# LPM_CLK.net
KiCad netlist of a schematic drawn in Altium Designer
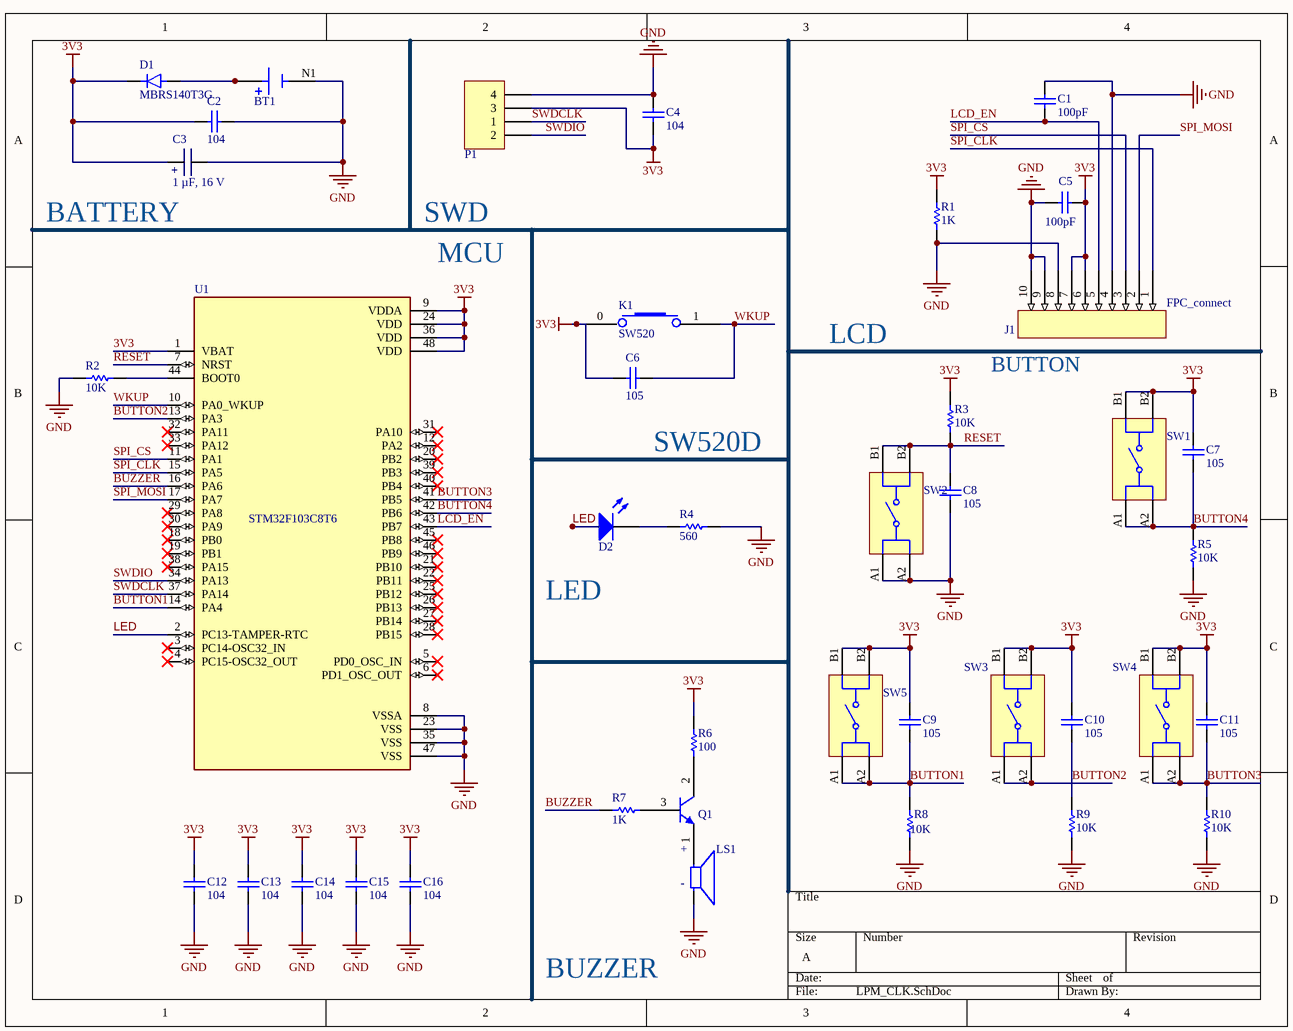
[diagram p0: LPM_CLK.SchDoc]

(export (version "E")
  (design (tool "Eeschema 10.0.6"))
  (components
    (comp (ref "BT1")
      (value "BAT-HLD-001")
      (footprint "BAT_BAT-HLD-001")
      (description "Battery Retainer Coin, 20.0mm 1 Cell SMD (SMT) Tab")
      (libsource (lib "BAT-HLD-001") (part "BAT-HLD-001"))
    )
    (comp (ref "C1")
      (value "100pF")
      (footprint "CAP-SM-0805")
      (description "Capacitor")
      (fields (field (name "Comment") "Cap Non-Pol SMD"))
      (libsource (lib "PIF_Library") (part "Cap Non-Pol SMD"))
    )
    (comp (ref "C2")
      (value "104")
      (footprint "CAP-SM-0805")
      (description "Capacitor")
      (fields (field (name "Comment") "Cap Non-Pol SMD"))
      (libsource (lib "PIF_Library") (part "Cap Non-Pol SMD"))
    )
    (comp (ref "C3")
      (value "1 µF, 16 V")
      (footprint "TANTALUM SMD A")
      (description "CAP TANT 1uF 10% 16V 1206")
      (libsource (lib "Altium_Tanta_Capacitor") (part "01120610510"))
    )
    (comp (ref "C4")
      (value "104")
      (footprint "CAP-SM-0805")
      (description "Capacitor")
      (fields (field (name "Comment") "Cap Non-Pol SMD"))
      (libsource (lib "PIF_Library") (part "Cap Non-Pol SMD"))
    )
    (comp (ref "C5")
      (value "100pF")
      (footprint "CAP-SM-0805")
      (description "Capacitor")
      (fields (field (name "Comment") "Cap Non-Pol SMD"))
      (libsource (lib "PIF_Library") (part "Cap Non-Pol SMD"))
    )
    (comp (ref "C6")
      (value "105")
      (footprint "CAP-SM-0805")
      (description "Capacitor")
      (fields (field (name "Comment") "Cap Non-Pol SMD"))
      (libsource (lib "PIF_Library") (part "Cap Non-Pol SMD"))
    )
    (comp (ref "C7")
      (value "105")
      (footprint "CAP-SM-0805")
      (description "Capacitor")
      (fields (field (name "Comment") "Cap Non-Pol SMD"))
      (libsource (lib "PIF_Library") (part "Cap Non-Pol SMD"))
    )
    (comp (ref "C8")
      (value "105")
      (footprint "CAP-SM-0805")
      (description "Capacitor")
      (fields (field (name "Comment") "Cap Non-Pol SMD"))
      (libsource (lib "PIF_Library") (part "Cap Non-Pol SMD"))
    )
    (comp (ref "C9")
      (value "105")
      (footprint "CAP-SM-0805")
      (description "Capacitor")
      (fields (field (name "Comment") "Cap Non-Pol SMD"))
      (libsource (lib "PIF_Library") (part "Cap Non-Pol SMD"))
    )
    (comp (ref "C10")
      (value "105")
      (footprint "CAP-SM-0805")
      (description "Capacitor")
      (fields (field (name "Comment") "Cap Non-Pol SMD"))
      (libsource (lib "PIF_Library") (part "Cap Non-Pol SMD"))
    )
    (comp (ref "C11")
      (value "105")
      (footprint "CAP-SM-0805")
      (description "Capacitor")
      (fields (field (name "Comment") "Cap Non-Pol SMD"))
      (libsource (lib "PIF_Library") (part "Cap Non-Pol SMD"))
    )
    (comp (ref "C12")
      (value "104")
      (footprint "CAP-SM-0805")
      (description "Capacitor")
      (fields (field (name "Comment") "Cap Non-Pol SMD"))
      (libsource (lib "PIF_Library") (part "Cap Non-Pol SMD"))
    )
    (comp (ref "C13")
      (value "104")
      (footprint "CAP-SM-0805")
      (description "Capacitor")
      (fields (field (name "Comment") "Cap Non-Pol SMD"))
      (libsource (lib "") (part "Cap Non-Pol SMD_1"))
    )
    (comp (ref "C14")
      (value "104")
      (footprint "CAP-SM-0805")
      (description "Capacitor")
      (fields (field (name "Comment") "Cap Non-Pol SMD"))
      (libsource (lib "PIF_Library") (part "Cap Non-Pol SMD"))
    )
    (comp (ref "C15")
      (value "104")
      (footprint "CAP-SM-0805")
      (description "Capacitor")
      (fields (field (name "Comment") "Cap Non-Pol SMD"))
      (libsource (lib "PIF_Library") (part "Cap Non-Pol SMD"))
    )
    (comp (ref "C16")
      (value "104")
      (footprint "CAP-SM-0805")
      (description "Capacitor")
      (fields (field (name "Comment") "Cap Non-Pol SMD"))
      (libsource (lib "PIF_Library") (part "Cap Non-Pol SMD"))
    )
    (comp (ref "D1")
      (value "MBRS140T3G")
      (footprint "DIOM5435X247N")
      (libsource (lib "MBRS140T3G") (part "MBRS140T3G"))
    )
    (comp (ref "D2")
      (value "LED SMD")
      (footprint "LED_0603_Blue")
      (description "LED")
      (libsource (lib "PIF_Library") (part "LED SMD"))
    )
    (comp (ref "J1")
      (value "FPC_connect")
      (footprint "FPC_connect")
      (libsource (lib "Integrated_Library1") (part "FPC_connect"))
    )
    (comp (ref "K1") (value "SW520") (footprint "SW520D") (libsource (lib "SW520D") (part "SW520D")))
    (comp (ref "LS1")
      (value "CMT-7525-80-SMT-TR")
      (footprint "XDCR_CMT-7525-80-SMT-TR")
      (description "7.5 mm, 3.6 Vo-p, 80 dB, Surface Mount (SMT), Magnetic Audio Transducer Buzzer")
      (fields
        (field (name "DIGI-KEY_PART_NUMBER") "102-CMT-7525-80-SMT-TR-ND")
        (field (name "MF") "CUI Devices")
      )
      (libsource (lib "CMT-7525-80-SMT-TR") (part "CMT-7525-80-SMT-TR"))
    )
    (comp (ref "P1")
      (value "Header 4H")
      (footprint "JP4H")
      (description "Header, 4-Pin, Right Angle")
      (fields (field (name "PUBLISHER") "Altium Limited"))
      (libsource (lib "PIF_Library") (part "Header 4H"))
    )
    (comp (ref "Q1")
      (value "C1815")
      (footprint "SOT23B")
      (description "NPN Bipolar Transistor")
      (libsource (lib "PIF_Library") (part "C1815"))
    )
    (comp (ref "R1")
      (value "1K")
      (footprint "RES-SM-0603")
      (description "Resistor")
      (fields (field (name "Comment") "RESISTOR SMD"))
      (libsource (lib "PIF_Library") (part "RESISTOR SMD"))
    )
    (comp (ref "R2")
      (value "10K")
      (footprint "RES-SM-0603")
      (description "Resistor")
      (fields (field (name "Comment") "RESISTOR SMD"))
      (libsource (lib "PIF_Library") (part "RESISTOR SMD"))
    )
    (comp (ref "R3")
      (value "10K")
      (footprint "RES-SM-0603")
      (description "Resistor")
      (fields (field (name "Comment") "RESISTOR SMD"))
      (libsource (lib "PIF_Library") (part "RESISTOR SMD"))
    )
    (comp (ref "R4")
      (value "560")
      (footprint "RES-SM-0603")
      (description "Resistor")
      (fields (field (name "Comment") "RESISTOR SMD"))
      (libsource (lib "PIF_Library") (part "RESISTOR SMD"))
    )
    (comp (ref "R5")
      (value "10K")
      (footprint "RES-SM-0603")
      (description "Resistor")
      (fields (field (name "Comment") "RESISTOR SMD"))
      (libsource (lib "PIF_Library") (part "RESISTOR SMD"))
    )
    (comp (ref "R6")
      (value "100")
      (footprint "RES-SM-0603")
      (description "Resistor")
      (fields (field (name "Comment") "RESISTOR SMD"))
      (libsource (lib "PIF_Library") (part "RESISTOR SMD"))
    )
    (comp (ref "R7")
      (value "1K")
      (footprint "RES-SM-0603")
      (description "Resistor")
      (fields (field (name "Comment") "RESISTOR SMD"))
      (libsource (lib "PIF_Library") (part "RESISTOR SMD"))
    )
    (comp (ref "R8")
      (value "10K")
      (footprint "RES-SM-0603")
      (description "Resistor")
      (fields (field (name "Comment") "RESISTOR SMD"))
      (libsource (lib "PIF_Library") (part "RESISTOR SMD"))
    )
    (comp (ref "R9")
      (value "10K")
      (footprint "RES-SM-0603")
      (description "Resistor")
      (fields (field (name "Comment") "RESISTOR SMD"))
      (libsource (lib "PIF_Library") (part "RESISTOR SMD"))
    )
    (comp (ref "R10")
      (value "10K")
      (footprint "RES-SM-0603")
      (description "Resistor")
      (fields (field (name "Comment") "RESISTOR SMD"))
      (libsource (lib "PIF_Library") (part "RESISTOR SMD"))
    )
    (comp (ref "SW1")
      (value "430451035836")
      (footprint "WS-TASV_L6W6H3.5_4304x10358x6")
      (description "WS-TASV SMT Washable Tact Switch, L6 x W6 x H3.5mm, 360g, SPST-NO, 12V, 50mA")
      (fields (field (name "MANUFACTURER") "Wurth Elektronik"))
      (libsource (lib "Altium_Button") (part "430451035836"))
    )
    (comp (ref "SW2")
      (value "430451035836")
      (footprint "WS-TASV_L6W6H3.5_4304x10358x6")
      (description "WS-TASV SMT Washable Tact Switch, L6 x W6 x H3.5mm, 360g, SPST-NO, 12V, 50mA")
      (fields (field (name "MANUFACTURER") "Wurth Elektronik"))
      (libsource (lib "Altium_Button") (part "430451035836"))
    )
    (comp (ref "SW3")
      (value "430451035836")
      (footprint "WS-TASV_L6W6H3.5_4304x10358x6")
      (description "WS-TASV SMT Washable Tact Switch, L6 x W6 x H3.5mm, 360g, SPST-NO, 12V, 50mA")
      (fields (field (name "MANUFACTURER") "Wurth Elektronik"))
      (libsource (lib "Altium_Button") (part "430451035836"))
    )
    (comp (ref "SW4")
      (value "430451035836")
      (footprint "WS-TASV_L6W6H3.5_4304x10358x6")
      (description "WS-TASV SMT Washable Tact Switch, L6 x W6 x H3.5mm, 360g, SPST-NO, 12V, 50mA")
      (fields (field (name "MANUFACTURER") "Wurth Elektronik"))
      (libsource (lib "Altium_Button") (part "430451035836"))
    )
    (comp (ref "SW5")
      (value "430451035836")
      (footprint "WS-TASV_L6W6H3.5_4304x10358x6")
      (description "WS-TASV SMT Washable Tact Switch, L6 x W6 x H3.5mm, 360g, SPST-NO, 12V, 50mA")
      (fields (field (name "MANUFACTURER") "Wurth Elektronik"))
      (libsource (lib "Altium_Button") (part "430451035836"))
    )
    (comp (ref "U1")
      (value "STM32F103C8T6")
      (footprint "QFP50P900X900X160-48N")
      (description "ARMÂ® CortexÂ®-M3 STM32F1 Microcontroller IC 32-Bit 72MHz 64KB (64K x 8) FLASH 48-LQFP (7x7)")
      (fields (field (name "MF") "STMicroelectronics"))
      (libsource (lib "STM32F103C8T6") (part "STM32F103C8T6"))
    )
  )
  (nets
    (net (code "1") (name "/BUTTON1") (class "Default")
      (node (ref "C9") (pin "1") (pinfunction "1_1") (pintype "passive"))
      (node (ref "R8") (pin "2") (pinfunction "2_2") (pintype "passive"))
      (node (ref "SW5") (pin "A1") (pinfunction "A1_A1") (pintype "passive"))
      (node (ref "SW5") (pin "A2") (pinfunction "A2_A2") (pintype "passive"))
      (node (ref "U1") (pin "14") (pinfunction "PA4_14") (pintype "bidirectional"))
    )
    (net (code "2") (name "/BUTTON2") (class "Default")
      (node (ref "C10") (pin "1") (pinfunction "1_1") (pintype "passive"))
      (node (ref "R9") (pin "2") (pinfunction "2_2") (pintype "passive"))
      (node (ref "SW3") (pin "A1") (pinfunction "A1_A1") (pintype "passive"))
      (node (ref "SW3") (pin "A2") (pinfunction "A2_A2") (pintype "passive"))
      (node (ref "U1") (pin "13") (pinfunction "PA3_13") (pintype "bidirectional"))
    )
    (net (code "3") (name "/BUTTON3") (class "Default")
      (node (ref "C11") (pin "1") (pinfunction "1_1") (pintype "passive"))
      (node (ref "R10") (pin "2") (pinfunction "2_2") (pintype "passive"))
      (node (ref "SW4") (pin "A1") (pinfunction "A1_A1") (pintype "passive"))
      (node (ref "SW4") (pin "A2") (pinfunction "A2_A2") (pintype "passive"))
      (node (ref "U1") (pin "41") (pinfunction "PB5_41") (pintype "bidirectional"))
    )
    (net (code "4") (name "/BUTTON4") (class "Default")
      (node (ref "C7") (pin "1") (pinfunction "1_1") (pintype "passive"))
      (node (ref "R5") (pin "2") (pinfunction "2_2") (pintype "passive"))
      (node (ref "SW1") (pin "A1") (pinfunction "A1_A1") (pintype "passive"))
      (node (ref "SW1") (pin "A2") (pinfunction "A2_A2") (pintype "passive"))
      (node (ref "U1") (pin "42") (pinfunction "PB6_42") (pintype "bidirectional"))
    )
    (net (code "5") (name "/BUZZER") (class "Default")
      (node (ref "R7") (pin "1") (pinfunction "1_1") (pintype "passive"))
      (node (ref "U1") (pin "16") (pinfunction "PA6_16") (pintype "bidirectional"))
    )
    (net (code "6") (name "/LCD_EN") (class "Default")
      (node (ref "C1") (pin "2") (pinfunction "2_2") (pintype "passive"))
      (node (ref "J1") (pin "5") (pintype "input"))
      (node (ref "U1") (pin "43") (pinfunction "PB7_43") (pintype "bidirectional"))
    )
    (net (code "7") (name "/LED") (class "Default")
      (node (ref "D2") (pin "1") (pinfunction "A_1") (pintype "passive"))
      (node (ref "U1") (pin "2") (pinfunction "PC13-TAMPER-RTC_2") (pintype "bidirectional"))
    )
    (net (code "8") (name "/RESET") (class "Default")
      (node (ref "C8") (pin "2") (pinfunction "2_2") (pintype "passive"))
      (node (ref "R3") (pin "1") (pinfunction "1_1") (pintype "passive"))
      (node (ref "SW2") (pin "B1") (pinfunction "B1_B1") (pintype "passive"))
      (node (ref "SW2") (pin "B2") (pinfunction "B2_B2") (pintype "passive"))
      (node (ref "U1") (pin "7") (pinfunction "NRST_7") (pintype "bidirectional"))
    )
    (net (code "9") (name "/SPI_CLK") (class "Default")
      (node (ref "J1") (pin "1") (pintype "input"))
      (node (ref "U1") (pin "15") (pinfunction "PA5_15") (pintype "bidirectional"))
    )
    (net (code "10") (name "/SPI_CS") (class "Default")
      (node (ref "J1") (pin "3") (pintype "input"))
      (node (ref "U1") (pin "11") (pinfunction "PA1_11") (pintype "bidirectional"))
    )
    (net (code "11") (name "/SPI_MOSI") (class "Default")
      (node (ref "J1") (pin "2") (pintype "input"))
      (node (ref "U1") (pin "17") (pinfunction "PA7_17") (pintype "bidirectional"))
    )
    (net (code "12") (name "/SWDCLK") (class "Default")
      (node (ref "P1") (pin "1") (pinfunction "1_1") (pintype "passive"))
      (node (ref "U1") (pin "37") (pinfunction "PA14_37") (pintype "bidirectional"))
    )
    (net (code "13") (name "/SWDIO") (class "Default")
      (node (ref "P1") (pin "2") (pinfunction "2_2") (pintype "passive"))
      (node (ref "U1") (pin "34") (pinfunction "PA13_34") (pintype "bidirectional"))
    )
    (net (code "14") (name "/WKUP") (class "Default")
      (node (ref "C6") (pin "1") (pinfunction "1_1") (pintype "passive"))
      (node (ref "K1") (pin "1") (pinfunction "-_1") (pintype "passive"))
      (node (ref "U1") (pin "10") (pinfunction "PA0_WKUP_10") (pintype "bidirectional"))
    )
    (net (code "15") (name "3V3") (class "Default")
      (node (ref "C10") (pin "2") (pinfunction "2_2") (pintype "passive"))
      (node (ref "C11") (pin "2") (pinfunction "2_2") (pintype "passive"))
      (node (ref "C12") (pin "2") (pinfunction "2_2") (pintype "passive"))
      (node (ref "C13") (pin "1") (pinfunction "1_1") (pintype "passive"))
      (node (ref "C14") (pin "2") (pinfunction "2_2") (pintype "passive"))
      (node (ref "C15") (pin "2") (pinfunction "2_2") (pintype "passive"))
      (node (ref "C16") (pin "2") (pinfunction "2_2") (pintype "passive"))
      (node (ref "C2") (pin "1") (pinfunction "1_1") (pintype "passive"))
      (node (ref "C3") (pin "2") (pinfunction "2_2") (pintype "passive"))
      (node (ref "C4") (pin "1") (pinfunction "1_1") (pintype "passive"))
      (node (ref "C5") (pin "1") (pinfunction "1_1") (pintype "passive"))
      (node (ref "C6") (pin "2") (pinfunction "2_2") (pintype "passive"))
      (node (ref "C7") (pin "2") (pinfunction "2_2") (pintype "passive"))
      (node (ref "C9") (pin "2") (pinfunction "2_2") (pintype "passive"))
      (node (ref "D1") (pin "1") (pinfunction "C_1") (pintype "passive"))
      (node (ref "J1") (pin "6") (pintype "input"))
      (node (ref "J1") (pin "7") (pintype "input"))
      (node (ref "K1") (pin "0") (pinfunction "+_0") (pintype "passive"))
      (node (ref "P1") (pin "3") (pinfunction "3_3") (pintype "passive"))
      (node (ref "R1") (pin "2") (pinfunction "2_2") (pintype "passive"))
      (node (ref "R3") (pin "2") (pinfunction "2_2") (pintype "passive"))
      (node (ref "R6") (pin "2") (pinfunction "2_2") (pintype "passive"))
      (node (ref "SW1") (pin "B1") (pinfunction "B1_B1") (pintype "passive"))
      (node (ref "SW1") (pin "B2") (pinfunction "B2_B2") (pintype "passive"))
      (node (ref "SW3") (pin "B1") (pinfunction "B1_B1") (pintype "passive"))
      (node (ref "SW3") (pin "B2") (pinfunction "B2_B2") (pintype "passive"))
      (node (ref "SW4") (pin "B1") (pinfunction "B1_B1") (pintype "passive"))
      (node (ref "SW4") (pin "B2") (pinfunction "B2_B2") (pintype "passive"))
      (node (ref "SW5") (pin "B1") (pinfunction "B1_B1") (pintype "passive"))
      (node (ref "SW5") (pin "B2") (pinfunction "B2_B2") (pintype "passive"))
      (node (ref "U1") (pin "1") (pinfunction "VBAT_1") (pintype "passive"))
      (node (ref "U1") (pin "24") (pinfunction "VDD_24") (pintype "power_in"))
      (node (ref "U1") (pin "36") (pinfunction "VDD_36") (pintype "power_in"))
      (node (ref "U1") (pin "48") (pinfunction "VDD_48") (pintype "power_in"))
      (node (ref "U1") (pin "9") (pinfunction "VDDA_9") (pintype "power_in"))
    )
    (net (code "16") (name "GND") (class "Default")
      (node (ref "BT1") (pin "N1") (pinfunction "NEG_N1") (pintype "passive"))
      (node (ref "C1") (pin "1") (pinfunction "1_1") (pintype "passive"))
      (node (ref "C12") (pin "1") (pinfunction "1_1") (pintype "passive"))
      (node (ref "C13") (pin "2") (pinfunction "2_2") (pintype "passive"))
      (node (ref "C14") (pin "1") (pinfunction "1_1") (pintype "passive"))
      (node (ref "C15") (pin "1") (pinfunction "1_1") (pintype "passive"))
      (node (ref "C16") (pin "1") (pinfunction "1_1") (pintype "passive"))
      (node (ref "C2") (pin "2") (pinfunction "2_2") (pintype "passive"))
      (node (ref "C3") (pin "1") (pinfunction "1_1") (pintype "passive"))
      (node (ref "C4") (pin "2") (pinfunction "2_2") (pintype "passive"))
      (node (ref "C5") (pin "2") (pinfunction "2_2") (pintype "passive"))
      (node (ref "C8") (pin "1") (pinfunction "1_1") (pintype "passive"))
      (node (ref "J1") (pin "10") (pintype "input"))
      (node (ref "J1") (pin "4") (pintype "input"))
      (node (ref "J1") (pin "8") (pintype "input"))
      (node (ref "J1") (pin "9") (pintype "input"))
      (node (ref "LS1") (pin "N") (pinfunction "N_N") (pintype "passive"))
      (node (ref "P1") (pin "4") (pinfunction "4_4") (pintype "passive"))
      (node (ref "R1") (pin "1") (pinfunction "1_1") (pintype "passive"))
      (node (ref "R10") (pin "1") (pinfunction "1_1") (pintype "passive"))
      (node (ref "R2") (pin "1") (pinfunction "1_1") (pintype "passive"))
      (node (ref "R4") (pin "2") (pinfunction "2_2") (pintype "passive"))
      (node (ref "R5") (pin "1") (pinfunction "1_1") (pintype "passive"))
      (node (ref "R8") (pin "1") (pinfunction "1_1") (pintype "passive"))
      (node (ref "R9") (pin "1") (pinfunction "1_1") (pintype "passive"))
      (node (ref "SW2") (pin "A1") (pinfunction "A1_A1") (pintype "passive"))
      (node (ref "SW2") (pin "A2") (pinfunction "A2_A2") (pintype "passive"))
      (node (ref "U1") (pin "23") (pinfunction "VSS_23") (pintype "power_in"))
      (node (ref "U1") (pin "35") (pinfunction "VSS_35") (pintype "power_in"))
      (node (ref "U1") (pin "47") (pinfunction "VSS_47") (pintype "power_in"))
      (node (ref "U1") (pin "8") (pinfunction "VSSA_8") (pintype "power_in"))
    )
    (net (code "17") (name "Net-(D1-A)") (class "Default")
      (node (ref "BT1") (pin "P1") (pinfunction "POS_P1") (pintype "passive"))
      (node (ref "BT1") (pin "P2") (pinfunction "POS_P2") (pintype "passive"))
      (node (ref "D1") (pin "2") (pinfunction "A_2") (pintype "passive"))
    )
    (net (code "18") (name "Net-(D2-K)") (class "Default")
      (node (ref "D2") (pin "2") (pinfunction "K_2") (pintype "passive"))
      (node (ref "R4") (pin "1") (pinfunction "1_1") (pintype "passive"))
    )
    (net (code "19") (name "Net-(Q1-B)") (class "Default")
      (node (ref "Q1") (pin "3") (pinfunction "B_3") (pintype "passive"))
      (node (ref "R7") (pin "2") (pinfunction "2_2") (pintype "passive"))
    )
    (net (code "20") (name "Net-(Q1-C)") (class "Default")
      (node (ref "Q1") (pin "2") (pinfunction "C_2") (pintype "passive"))
      (node (ref "R6") (pin "1") (pinfunction "1_1") (pintype "passive"))
    )
    (net (code "21") (name "Net-(Q1-E)") (class "Default")
      (node (ref "LS1") (pin "P") (pinfunction "P_P") (pintype "passive"))
      (node (ref "Q1") (pin "1") (pinfunction "E_1") (pintype "passive"))
    )
    (net (code "22") (name "Net-(U1-BOOT0)") (class "Default")
      (node (ref "R2") (pin "2") (pinfunction "2_2") (pintype "passive"))
      (node (ref "U1") (pin "44") (pinfunction "BOOT0_44") (pintype "passive"))
    )
    (net (code "23") (name "unconnected-(U1-PA2-Pad12)") (class "Default")
      (node (ref "U1") (pin "12") (pinfunction "PA2_12") (pintype "bidirectional+no_connect"))
    )
    (net (code "24") (name "unconnected-(U1-PA8-Pad29)") (class "Default")
      (node (ref "U1") (pin "29") (pinfunction "PA8_29") (pintype "bidirectional+no_connect"))
    )
    (net (code "25") (name "unconnected-(U1-PA9-Pad30)") (class "Default")
      (node (ref "U1") (pin "30") (pinfunction "PA9_30") (pintype "bidirectional+no_connect"))
    )
    (net (code "26") (name "unconnected-(U1-PA10-Pad31)") (class "Default")
      (node (ref "U1") (pin "31") (pinfunction "PA10_31") (pintype "bidirectional+no_connect"))
    )
    (net (code "27") (name "unconnected-(U1-PA11-Pad32)") (class "Default")
      (node (ref "U1") (pin "32") (pinfunction "PA11_32") (pintype "bidirectional+no_connect"))
    )
    (net (code "28") (name "unconnected-(U1-PA12-Pad33)") (class "Default")
      (node (ref "U1") (pin "33") (pinfunction "PA12_33") (pintype "bidirectional+no_connect"))
    )
    (net (code "29") (name "unconnected-(U1-PA15-Pad38)") (class "Default")
      (node (ref "U1") (pin "38") (pinfunction "PA15_38") (pintype "bidirectional+no_connect"))
    )
    (net (code "30") (name "unconnected-(U1-PB0-Pad18)") (class "Default")
      (node (ref "U1") (pin "18") (pinfunction "PB0_18") (pintype "bidirectional+no_connect"))
    )
    (net (code "31") (name "unconnected-(U1-PB1-Pad19)") (class "Default")
      (node (ref "U1") (pin "19") (pinfunction "PB1_19") (pintype "bidirectional+no_connect"))
    )
    (net (code "32") (name "unconnected-(U1-PB2-Pad20)") (class "Default")
      (node (ref "U1") (pin "20") (pinfunction "PB2_20") (pintype "bidirectional+no_connect"))
    )
    (net (code "33") (name "unconnected-(U1-PB3-Pad39)") (class "Default")
      (node (ref "U1") (pin "39") (pinfunction "PB3_39") (pintype "bidirectional+no_connect"))
    )
    (net (code "34") (name "unconnected-(U1-PB4-Pad40)") (class "Default")
      (node (ref "U1") (pin "40") (pinfunction "PB4_40") (pintype "bidirectional+no_connect"))
    )
    (net (code "35") (name "unconnected-(U1-PB8-Pad45)") (class "Default")
      (node (ref "U1") (pin "45") (pinfunction "PB8_45") (pintype "bidirectional+no_connect"))
    )
    (net (code "36") (name "unconnected-(U1-PB9-Pad46)") (class "Default")
      (node (ref "U1") (pin "46") (pinfunction "PB9_46") (pintype "bidirectional+no_connect"))
    )
    (net (code "37") (name "unconnected-(U1-PB10-Pad21)") (class "Default")
      (node (ref "U1") (pin "21") (pinfunction "PB10_21") (pintype "bidirectional+no_connect"))
    )
    (net (code "38") (name "unconnected-(U1-PB11-Pad22)") (class "Default")
      (node (ref "U1") (pin "22") (pinfunction "PB11_22") (pintype "bidirectional+no_connect"))
    )
    (net (code "39") (name "unconnected-(U1-PB12-Pad25)") (class "Default")
      (node (ref "U1") (pin "25") (pinfunction "PB12_25") (pintype "bidirectional+no_connect"))
    )
    (net (code "40") (name "unconnected-(U1-PB13-Pad26)") (class "Default")
      (node (ref "U1") (pin "26") (pinfunction "PB13_26") (pintype "bidirectional+no_connect"))
    )
    (net (code "41") (name "unconnected-(U1-PB14-Pad27)") (class "Default")
      (node (ref "U1") (pin "27") (pinfunction "PB14_27") (pintype "bidirectional+no_connect"))
    )
    (net (code "42") (name "unconnected-(U1-PB15-Pad28)") (class "Default")
      (node (ref "U1") (pin "28") (pinfunction "PB15_28") (pintype "bidirectional+no_connect"))
    )
    (net (code "43") (name "unconnected-(U1-PC14-OSC32_IN-Pad3)") (class "Default")
      (node (ref "U1") (pin "3") (pinfunction "PC14-OSC32_IN_3") (pintype "bidirectional+no_connect"))
    )
    (net (code "44") (name "unconnected-(U1-PC15-OSC32_OUT-Pad4)") (class "Default")
      (node (ref "U1") (pin "4") (pinfunction "PC15-OSC32_OUT_4") (pintype "bidirectional+no_connect"))
    )
    (net (code "45") (name "unconnected-(U1-PD0_OSC_IN-Pad5)") (class "Default")
      (node (ref "U1") (pin "5") (pinfunction "PD0_OSC_IN_5") (pintype "bidirectional+no_connect"))
    )
    (net (code "46") (name "unconnected-(U1-PD1_OSC_OUT-Pad6)") (class "Default")
      (node (ref "U1") (pin "6") (pinfunction "PD1_OSC_OUT_6") (pintype "bidirectional+no_connect"))
    )
  )
)
